# ISO_Power.net
KiCad netlist of a schematic drawn in Altium Designer
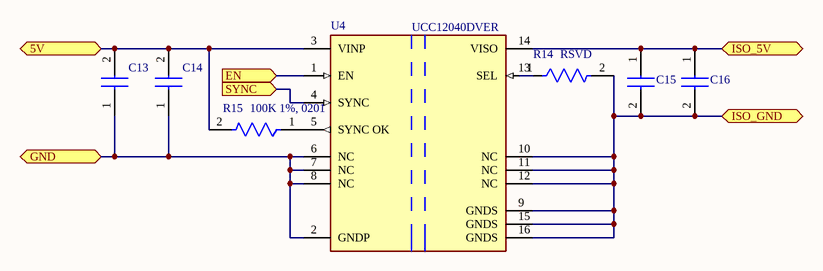
[diagram p0: ISO_Power.SchDoc]

(export (version "E")
  (design (tool "Eeschema 10.0.6"))
  (components
    (comp (ref "C13")
      (value "10 uF, 25V, X6S, 0402")
      (footprint "SamacSys:CAPC1005X70N")
      (description "Capacitor")
      (fields
        (field (name "MANUFACTURER_PART_NUMBER") "GRM155F51E104ZA01E")
        (field (name "MOUSER PART NUMBER") "81-GRM15F51E104ZA01E")
      )
      (libsource (lib "*") (part "GRM155F51E104ZA01E"))
    )
    (comp (ref "C14")
      (value "100 nF, 25V, X6S, 0201")
      (footprint "SamacSys:CAPC0603X33N")
      (description "Capacitor")
      (fields
        (field (name "MANUFACTURER_PART_NUMBER") "GRM033C81E104KE14D")
        (field (name "MOUSER PART NUMBER") "81-GRM33C81E104KE14D")
      )
      (libsource (lib "*") (part "GRM033C81E104KE14D"))
    )
    (comp (ref "C15")
      (value "100 nF, 25V, X6S, 0201")
      (footprint "SamacSys:CAPC0603X33N")
      (description "Capacitor")
      (fields
        (field (name "MANUFACTURER_PART_NUMBER") "GRM033C81E104KE14D")
        (field (name "MOUSER PART NUMBER") "81-GRM33C81E104KE14D")
      )
      (libsource (lib "*") (part "GRM033C81E104KE14D"))
    )
    (comp (ref "C16")
      (value "10 uF, 25V, X6S, 0402")
      (footprint "SamacSys:CAPC1005X70N")
      (description "Capacitor")
      (fields
        (field (name "MANUFACTURER_PART_NUMBER") "GRM155F51E104ZA01E")
        (field (name "MOUSER PART NUMBER") "81-GRM15F51E104ZA01E")
      )
      (libsource (lib "*") (part "GRM155F51E104ZA01E"))
    )
    (comp (ref "R14")
      (value "RSVD")
      (footprint "FP-ERJ1GN-IPC_A")
      (description "RES SMD 100K OHM 1% 1/20W 0201")
      (fields (field (name "TOLERANCE") "1%"))
      (libsource (lib "Altium Content Vault") (part "1029c3af85768c4190bb7ad29bc67b5"))
    )
    (comp (ref "R15")
      (value "100K 1%, 0201")
      (footprint "FP-ERJ1GN-IPC_A")
      (description "RES SMD 100K OHM 1% 1/20W 0201")
      (fields (field (name "TOLERANCE") "1%"))
      (libsource (lib "Altium Content Vault") (part "1029c3af85768c4190bb7ad29bc67b5"))
    )
    (comp (ref "U4")
      (value "UCC12040DVER")
      (footprint "FP-DVE0016A-MFG")
      (description "DC DC CONVERTER 3.3V 5V 500MW")
      (libsource (lib "Altium Content Vault") (part "cf9dcfd4a8b3775ff5e4cba6f3e7206"))
    )
  )
  (nets
    (net (code "1") (name "/5V") (class "Default")
      (node (ref "C13") (pin "2") (pinfunction "2_2") (pintype "passive"))
      (node (ref "C14") (pin "2") (pinfunction "2_2") (pintype "passive"))
      (node (ref "R15") (pin "2") (pinfunction "2_2") (pintype "passive"))
      (node (ref "U4") (pin "3") (pinfunction "VINP_3") (pintype "power_in"))
    )
    (net (code "2") (name "/EN") (class "Default")
      (node (ref "U4") (pin "1") (pinfunction "EN_1") (pintype "input"))
    )
    (net (code "3") (name "/GND") (class "Default")
      (node (ref "C13") (pin "1") (pinfunction "1_1") (pintype "passive"))
      (node (ref "C14") (pin "1") (pinfunction "1_1") (pintype "passive"))
      (node (ref "U4") (pin "2") (pinfunction "GNDP_2") (pintype "power_in"))
      (node (ref "U4") (pin "6") (pinfunction "NC_6") (pintype "passive"))
      (node (ref "U4") (pin "7") (pinfunction "NC_7") (pintype "passive"))
      (node (ref "U4") (pin "8") (pinfunction "NC_8") (pintype "passive"))
    )
    (net (code "4") (name "/ISO_5V") (class "Default")
      (node (ref "C15") (pin "1") (pinfunction "1_1") (pintype "passive"))
      (node (ref "C16") (pin "1") (pinfunction "1_1") (pintype "passive"))
      (node (ref "U4") (pin "14") (pinfunction "VISO_14") (pintype "power_in"))
    )
    (net (code "5") (name "/ISO_GND") (class "Default")
      (node (ref "C15") (pin "2") (pinfunction "2_2") (pintype "passive"))
      (node (ref "C16") (pin "2") (pinfunction "2_2") (pintype "passive"))
      (node (ref "R14") (pin "2") (pinfunction "2_2") (pintype "passive"))
      (node (ref "U4") (pin "10") (pinfunction "NC_10") (pintype "passive"))
      (node (ref "U4") (pin "11") (pinfunction "NC_11") (pintype "passive"))
      (node (ref "U4") (pin "12") (pinfunction "NC_12") (pintype "passive"))
      (node (ref "U4") (pin "15") (pinfunction "GNDS_15") (pintype "power_in"))
      (node (ref "U4") (pin "16") (pinfunction "GNDS_16") (pintype "power_in"))
      (node (ref "U4") (pin "9") (pinfunction "GNDS_9") (pintype "power_in"))
    )
    (net (code "6") (name "/SYNC") (class "Default")
      (node (ref "U4") (pin "4") (pinfunction "SYNC_4") (pintype "input"))
    )
    (net (code "7") (name "Net-(U4-SEL)") (class "Default")
      (node (ref "R14") (pin "1") (pinfunction "1_1") (pintype "passive"))
      (node (ref "U4") (pin "13") (pinfunction "SEL_13") (pintype "input"))
    )
    (net (code "8") (name "Net-(U4-SYNC_OK)") (class "Default")
      (node (ref "R15") (pin "1") (pinfunction "1_1") (pintype "passive"))
      (node (ref "U4") (pin "5") (pinfunction "SYNC_OK_5") (pintype "output"))
    )
  )
)
